# USB_SERIAL.net
KiCad netlist of a schematic drawn in Altium Designer
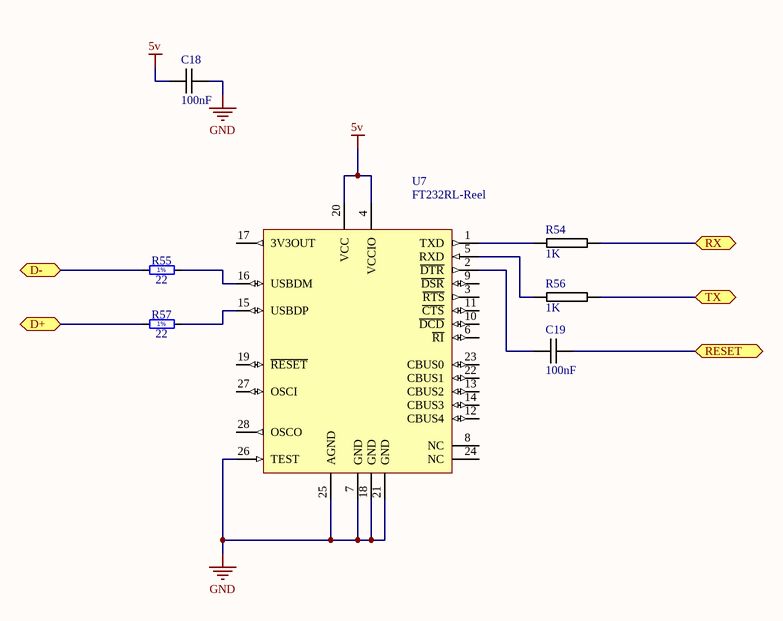
[diagram p0: USB_SERIAL.SchDoc]

(export (version "E")
  (design (tool "Eeschema 10.0.6"))
  (components
    (comp (ref "C18")
      (value "100nF")
      (footprint "0805C-TBD")
      (description "CAPACITOR 0805 CERAMIC")
      (libsource (lib "vh_altium_library") (part "0805C-100nF-25V-X7R-MUR"))
    )
    (comp (ref "C19")
      (value "100nF")
      (footprint "0805C-TBD")
      (description "CAPACITOR 0805 CERAMIC")
      (libsource (lib "vh_altium_library") (part "0805C-100nF-25V-X7R-MUR"))
    )
    (comp (ref "R54")
      (value "1K")
      (footprint "0805R-1K")
      (description "RESISTOR 0805 1/4 WATT THIN FILM")
      (libsource (lib "vh_altium_library") (part "0805R-1K"))
    )
    (comp (ref "R55")
      (value "22")
      (footprint "RESC2012X60N")
      (description "Resistor - 1%")
      (fields
        (field (name "PART NUMBER") "R0805_22R_1%_0.125W_100PPM")
        (field (name "POWER") "0.125W")
        (field (name "AUTHOR") "CERN DEM JLC")
      )
      (libsource (lib "Resistors") (part "Resistor - 1%"))
    )
    (comp (ref "R56")
      (value "1K")
      (footprint "0805R-1K")
      (description "RESISTOR 0805 1/4 WATT THIN FILM")
      (libsource (lib "vh_altium_library") (part "0805R-1K"))
    )
    (comp (ref "R57")
      (value "22")
      (footprint "RESC2012X60N")
      (description "Resistor - 1%")
      (fields
        (field (name "PART NUMBER") "R0805_22R_1%_0.125W_100PPM")
        (field (name "POWER") "0.125W")
        (field (name "AUTHOR") "CERN DEM JLC")
      )
      (libsource (lib "Resistors") (part "Resistor - 1%"))
    )
    (comp (ref "U7")
      (value "FT232RL-Reel")
      (footprint "SSOP-28_N")
      (description "USB UART Asynchronous Serial Data Transfer Chip, 28-pin SSOP, Tape and Reel")
      (fields (field (name "MANUFACTURER") "FTDI"))
      (libsource (lib "FTDI FT Series") (part "FT232RL-Reel"))
    )
  )
  (nets
    (net (code "1") (name "/D+") (class "Default")
      (node (ref "R57") (pin "1") (pinfunction "1_1") (pintype "passive"))
    )
    (net (code "2") (name "/D-") (class "Default")
      (node (ref "R55") (pin "1") (pinfunction "1_1") (pintype "passive"))
    )
    (net (code "3") (name "/RESET") (class "Default") (node (ref "C19") (pin "2") (pintype "passive")))
    (net (code "4") (name "/RX") (class "Default") (node (ref "R54") (pin "2") (pintype "passive")))
    (net (code "5") (name "/TX") (class "Default") (node (ref "R56") (pin "2") (pintype "passive")))
    (net (code "6") (name "5v") (class "Default")
      (node (ref "C18") (pin "1") (pintype "passive"))
      (node (ref "U7") (pin "20") (pinfunction "VCC_20") (pintype "power_in"))
      (node (ref "U7") (pin "4") (pinfunction "VCCIO_4") (pintype "power_in"))
    )
    (net (code "7") (name "GND") (class "Default")
      (node (ref "C18") (pin "2") (pintype "passive"))
      (node (ref "U7") (pin "18") (pinfunction "GND_18") (pintype "power_in"))
      (node (ref "U7") (pin "21") (pinfunction "GND_21") (pintype "power_in"))
      (node (ref "U7") (pin "25") (pinfunction "AGND_25") (pintype "power_in"))
      (node (ref "U7") (pin "26") (pinfunction "TEST_26") (pintype "input"))
      (node (ref "U7") (pin "7") (pinfunction "GND_7") (pintype "power_in"))
    )
    (net (code "8") (name "Net-(U7-RXD)") (class "Default")
      (node (ref "R56") (pin "1") (pintype "passive"))
      (node (ref "U7") (pin "5") (pinfunction "RXD_5") (pintype "input"))
    )
    (net (code "9") (name "Net-(U7-TXD)") (class "Default")
      (node (ref "R54") (pin "1") (pintype "passive"))
      (node (ref "U7") (pin "1") (pinfunction "TXD_1") (pintype "output"))
    )
    (net (code "10") (name "Net-(U7-USBDM)") (class "Default")
      (node (ref "R55") (pin "2") (pinfunction "2_2") (pintype "passive"))
      (node (ref "U7") (pin "16") (pinfunction "USBDM_16") (pintype "bidirectional"))
    )
    (net (code "11") (name "Net-(U7-USBDP)") (class "Default")
      (node (ref "R57") (pin "2") (pinfunction "2_2") (pintype "passive"))
      (node (ref "U7") (pin "15") (pinfunction "USBDP_15") (pintype "bidirectional"))
    )
    (net (code "12") (name "Net-(U7-~{DTR})") (class "Default")
      (node (ref "C19") (pin "1") (pintype "passive"))
      (node (ref "U7") (pin "2") (pinfunction "~{DTR}_2") (pintype "output"))
    )
    (net (code "13") (name "unconnected-(U7-3V3OUT-Pad17)") (class "Default")
      (node (ref "U7") (pin "17") (pinfunction "3V3OUT_17") (pintype "output"))
    )
    (net (code "14") (name "unconnected-(U7-CBUS0-Pad23)") (class "Default")
      (node (ref "U7") (pin "23") (pinfunction "CBUS0_23") (pintype "bidirectional"))
    )
    (net (code "15") (name "unconnected-(U7-CBUS1-Pad22)") (class "Default")
      (node (ref "U7") (pin "22") (pinfunction "CBUS1_22") (pintype "bidirectional"))
    )
    (net (code "16") (name "unconnected-(U7-CBUS2-Pad13)") (class "Default")
      (node (ref "U7") (pin "13") (pinfunction "CBUS2_13") (pintype "bidirectional"))
    )
    (net (code "17") (name "unconnected-(U7-CBUS3-Pad14)") (class "Default")
      (node (ref "U7") (pin "14") (pinfunction "CBUS3_14") (pintype "bidirectional"))
    )
    (net (code "18") (name "unconnected-(U7-CBUS4-Pad12)") (class "Default")
      (node (ref "U7") (pin "12") (pinfunction "CBUS4_12") (pintype "bidirectional"))
    )
    (net (code "19") (name "unconnected-(U7-NC-Pad8)") (class "Default")
      (node (ref "U7") (pin "8") (pinfunction "NC_8") (pintype "passive"))
    )
    (net (code "20") (name "unconnected-(U7-NC-Pad24)") (class "Default")
      (node (ref "U7") (pin "24") (pinfunction "NC_24") (pintype "passive"))
    )
    (net (code "21") (name "unconnected-(U7-OSCI-Pad27)") (class "Default")
      (node (ref "U7") (pin "27") (pinfunction "OSCI_27") (pintype "bidirectional"))
    )
    (net (code "22") (name "unconnected-(U7-OSCO-Pad28)") (class "Default")
      (node (ref "U7") (pin "28") (pinfunction "OSCO_28") (pintype "output"))
    )
    (net (code "23") (name "unconnected-(U7-~{CTS}-Pad11)") (class "Default")
      (node (ref "U7") (pin "11") (pinfunction "~{CTS}_11") (pintype "bidirectional"))
    )
    (net (code "24") (name "unconnected-(U7-~{DCD}-Pad10)") (class "Default")
      (node (ref "U7") (pin "10") (pinfunction "~{DCD}_10") (pintype "bidirectional"))
    )
    (net (code "25") (name "unconnected-(U7-~{DSR}-Pad9)") (class "Default")
      (node (ref "U7") (pin "9") (pinfunction "~{DSR}_9") (pintype "bidirectional"))
    )
    (net (code "26") (name "unconnected-(U7-~{RESET}-Pad19)") (class "Default")
      (node (ref "U7") (pin "19") (pinfunction "~{RESET}_19") (pintype "bidirectional"))
    )
    (net (code "27") (name "unconnected-(U7-~{RI}-Pad6)") (class "Default")
      (node (ref "U7") (pin "6") (pinfunction "~{RI}_6") (pintype "bidirectional"))
    )
    (net (code "28") (name "unconnected-(U7-~{RTS}-Pad3)") (class "Default")
      (node (ref "U7") (pin "3") (pinfunction "~{RTS}_3") (pintype "output"))
    )
  )
)
